# PK_MUV_L1.net
KiCad netlist of a schematic drawn in EAGLE
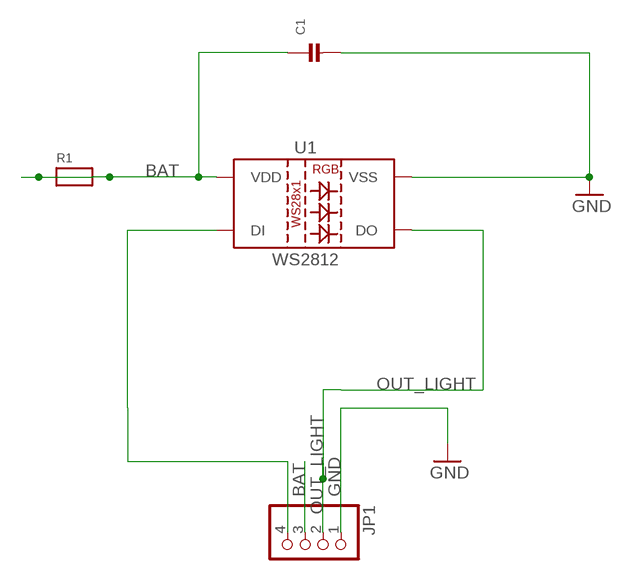
[diagram p0: schematic, sheet 1]

(export (version "E")
  (design (tool "Eeschema 10.0.6"))
  (components
    (comp (ref "C1")
      (value "CAP_CERAMIC1206")
      (footprint "eagle-import:1206")
      (libsource (lib "eagle-import") (part "CAP_CERAMIC1206"))
    )
    (comp (ref "JP1")
      (value "HEADER-1X4")
      (footprint "eagle-import:1X04_OVAL")
      (libsource (lib "eagle-import") (part "HEADER-1X4"))
    )
    (comp (ref "R1")
      (value "RESISTOR1206")
      (footprint "eagle-import:1206")
      (libsource (lib "eagle-import") (part "RESISTOR1206"))
    )
    (comp (ref "U1")
      (value "WS2812")
      (footprint "eagle-import:LED-TRICOLOR-5050-IC")
      (libsource (lib "eagle-import") (part "WS2812{dblquote}"))
    )
  )
  (nets
    (net (code "1") (name "/BAT") (class "Default")
      (node (ref "C1") (pin "1") (pinfunction "P$1_1") (pintype "passive"))
      (node (ref "JP1") (pin "3") (pinfunction "3_3") (pintype "passive"))
      (node (ref "R1") (pin "1") (pinfunction "1_1") (pintype "passive"))
      (node (ref "R1") (pin "2") (pinfunction "2_2") (pintype "passive"))
      (node (ref "U1") (pin "3") (pinfunction "VDD_3") (pintype "bidirectional"))
      (node (ref "U1") (pin "5") (pinfunction "VDD_5") (pintype "bidirectional"))
    )
    (net (code "2") (name "/OUT_LIGHT") (class "Default")
      (node (ref "JP1") (pin "2") (pinfunction "2_2") (pintype "passive"))
      (node (ref "U1") (pin "1") (pinfunction "DO_1") (pintype "bidirectional"))
    )
    (net (code "3") (name "GND") (class "Default")
      (node (ref "C1") (pin "2") (pinfunction "P$2_2") (pintype "passive"))
      (node (ref "JP1") (pin "1") (pinfunction "1_1") (pintype "passive"))
      (node (ref "U1") (pin "6") (pinfunction "VSS_6") (pintype "bidirectional"))
    )
    (net (code "4") (name "Net-(U1-DI)") (class "Default")
      (node (ref "JP1") (pin "4") (pinfunction "4_4") (pintype "passive"))
      (node (ref "U1") (pin "2") (pinfunction "DI_2") (pintype "bidirectional"))
    )
  )
)
